# Comparators.net
KiCad netlist of a schematic drawn in Altium Designer
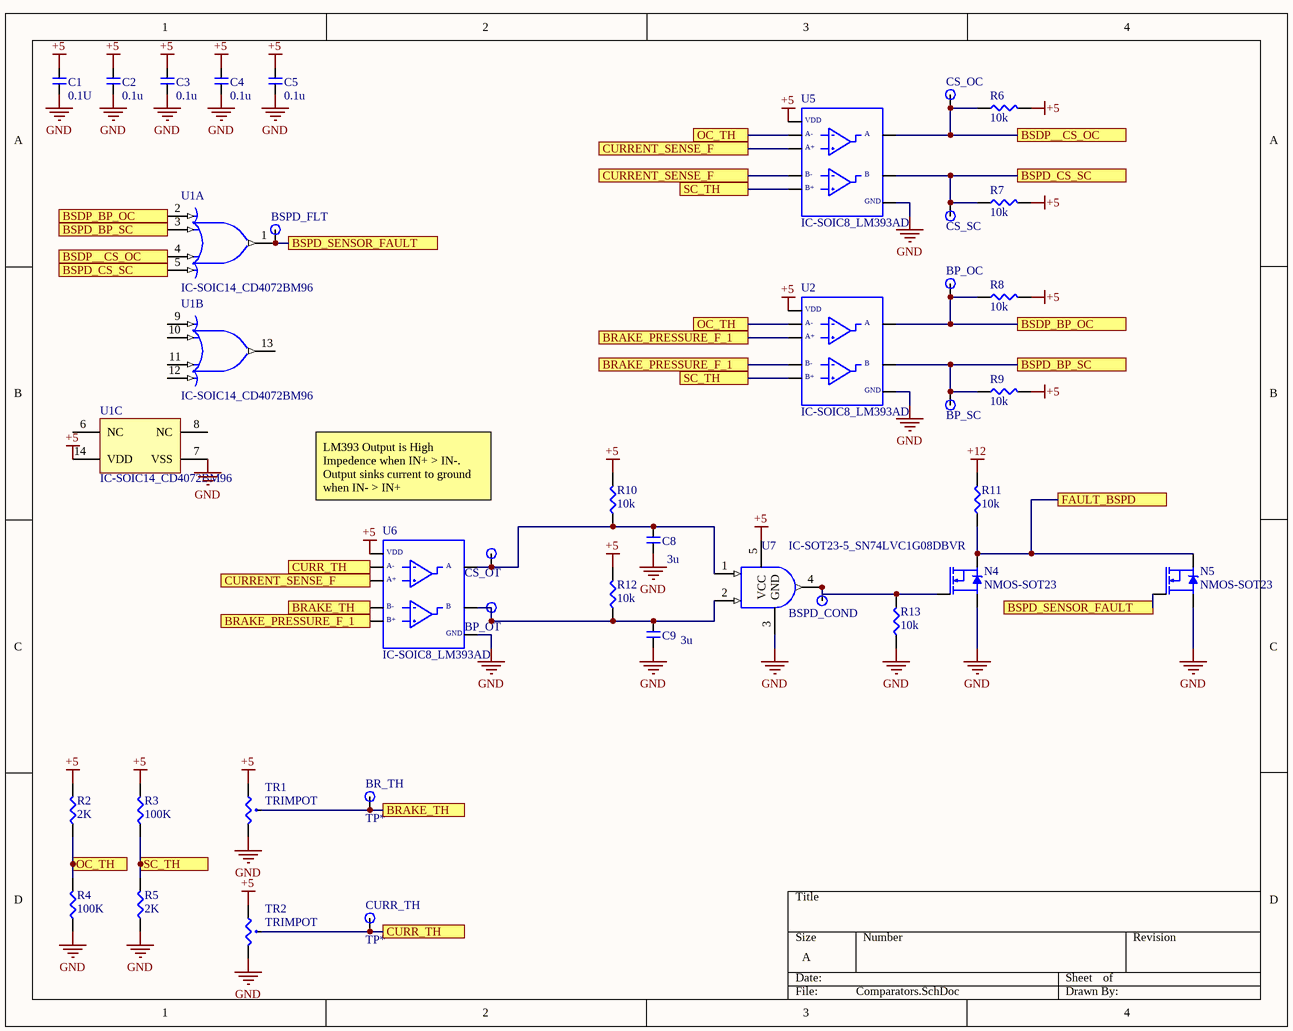
[diagram p0: Comparators.SchDoc]

(export (version "E")
  (design (tool "Eeschema 10.0.6"))
  (components
    (comp (ref "BP_OC")
      (value "~")
      (footprint "Testpoint")
      (libsource (lib "ife19_Elec_Library") (part "Testpoint"))
    )
    (comp (ref "BP_OT")
      (value "~")
      (footprint "Testpoint")
      (libsource (lib "ife19_Elec_Library") (part "Testpoint"))
    )
    (comp (ref "BP_SC")
      (value "~")
      (footprint "Testpoint")
      (libsource (lib "ife19_Elec_Library") (part "Testpoint"))
    )
    (comp (ref "BR_TH")
      (value "TP*")
      (footprint "Testpoint")
      (libsource (lib "ife19_Elec_Library") (part "Testpoint"))
    )
    (comp (ref "BSPD_COND")
      (value "~")
      (footprint "Testpoint")
      (libsource (lib "ife19_Elec_Library") (part "Testpoint"))
    )
    (comp (ref "BSPD_FLT")
      (value "~")
      (footprint "Testpoint")
      (libsource (lib "ife19_Elec_Library") (part "Testpoint"))
    )
    (comp (ref "C1")
      (value "0.1U")
      (footprint "ife19_Elec_Library:CAP-0603")
      (libsource (lib "ife19_Elec_Library") (part "CAP-0603"))
    )
    (comp (ref "C2")
      (value "0.1u")
      (footprint "CAP-0603")
      (libsource (lib "ife19_Elec_Library") (part "CAP-0603"))
    )
    (comp (ref "C3")
      (value "0.1u")
      (footprint "CAP-0603")
      (libsource (lib "ife19_Elec_Library") (part "CAP-0603"))
    )
    (comp (ref "C4")
      (value "0.1u")
      (footprint "CAP-0603")
      (libsource (lib "ife19_Elec_Library") (part "CAP-0603"))
    )
    (comp (ref "C5")
      (value "0.1u")
      (footprint "CAP-0603")
      (libsource (lib "ife19_Elec_Library") (part "CAP-0603"))
    )
    (comp (ref "C8")
      (value "3u")
      (footprint "CAP-0603")
      (libsource (lib "ife19_Elec_Library") (part "CAP-0603"))
    )
    (comp (ref "C9")
      (value "3u")
      (footprint "CAP-0603")
      (libsource (lib "ife19_Elec_Library") (part "CAP-0603"))
    )
    (comp (ref "CS_OC")
      (value "~")
      (footprint "Testpoint")
      (libsource (lib "ife19_Elec_Library") (part "Testpoint"))
    )
    (comp (ref "CS_OT")
      (value "~")
      (footprint "Testpoint")
      (libsource (lib "ife19_Elec_Library") (part "Testpoint"))
    )
    (comp (ref "CS_SC")
      (value "~")
      (footprint "Testpoint")
      (libsource (lib "ife19_Elec_Library") (part "Testpoint"))
    )
    (comp (ref "CURR_TH")
      (value "TP*")
      (footprint "Testpoint")
      (libsource (lib "ife19_Elec_Library") (part "Testpoint"))
    )
    (comp (ref "N4")
      (value "NMOS-SOT23")
      (footprint "SOT23")
      (libsource (lib "ife19_Elec_Library") (part "NMOS-SOT23"))
    )
    (comp (ref "N5")
      (value "NMOS-SOT23")
      (footprint "SOT23")
      (libsource (lib "ife19_Elec_Library") (part "NMOS-SOT23"))
    )
    (comp (ref "R2")
      (value "2K")
      (footprint "RES-0603")
      (libsource (lib "ife19_Elec_Library") (part "RES-0603"))
    )
    (comp (ref "R3")
      (value "100K")
      (footprint "RES-0603")
      (libsource (lib "ife19_Elec_Library") (part "RES-0603"))
    )
    (comp (ref "R4")
      (value "100K")
      (footprint "RES-0603")
      (libsource (lib "ife19_Elec_Library") (part "RES-0603"))
    )
    (comp (ref "R5")
      (value "2K")
      (footprint "RES-0603")
      (libsource (lib "ife19_Elec_Library") (part "RES-0603"))
    )
    (comp (ref "R6")
      (value "10k")
      (footprint "RES-0603")
      (libsource (lib "ife19_Elec_Library") (part "RES-0603"))
    )
    (comp (ref "R7")
      (value "10k")
      (footprint "RES-0603")
      (libsource (lib "ife19_Elec_Library") (part "RES-0603"))
    )
    (comp (ref "R8")
      (value "10k")
      (footprint "RES-0603")
      (libsource (lib "ife19_Elec_Library") (part "RES-0603"))
    )
    (comp (ref "R9")
      (value "10k")
      (footprint "RES-0603")
      (libsource (lib "ife19_Elec_Library") (part "RES-0603"))
    )
    (comp (ref "R10")
      (value "10k")
      (footprint "RES-0603")
      (libsource (lib "ife19_Elec_Library") (part "RES-0603"))
    )
    (comp (ref "R11")
      (value "10k")
      (footprint "RES-0603")
      (libsource (lib "ife19_Elec_Library") (part "RES-0603"))
    )
    (comp (ref "R12")
      (value "10k")
      (footprint "RES-0603")
      (libsource (lib "ife19_Elec_Library") (part "RES-0603"))
    )
    (comp (ref "R13")
      (value "10k")
      (footprint "RES-0603")
      (libsource (lib "ife19_Elec_Library") (part "RES-0603"))
    )
    (comp (ref "TR1")
      (value "TRIMPOT")
      (footprint "TRIMPOT_PV36W")
      (libsource (lib "ife19_Elec_Library") (part "TRIMPOT_PV36W"))
    )
    (comp (ref "TR2")
      (value "TRIMPOT")
      (footprint "TRIMPOT_PV36W")
      (libsource (lib "ife19_Elec_Library") (part "TRIMPOT_PV36W"))
    )
    (comp (ref "U1")
      (value "IC-SOIC14_CD4072BM96")
      (footprint "SOIC127P600X175-14N")
      (description "Logic Gates CMOS Dual 4-Input OR")
      (fields
        (field (name "MANUFACTURER PART NUMBER") "CD4072BM96")
        (field (name "MANUFACTURER") "Texas Instruments")
        (field (name "SOURCE") "ife19_Elec_Library.schlib")
      )
      (libsource (lib "Illini Formula Electric") (part "IC-SOIC14_CD4072BM96"))
    )
    (comp (ref "U2")
      (value "IC-SOIC8_LM393AD")
      (footprint "SOIC8")
      (libsource (lib "ife19_Elec_Library") (part "IC-SOIC8_LM393"))
    )
    (comp (ref "U5")
      (value "IC-SOIC8_LM393AD")
      (footprint "SOIC8")
      (libsource (lib "ife19_Elec_Library") (part "IC-SOIC8_LM393"))
    )
    (comp (ref "U6")
      (value "IC-SOIC8_LM393AD")
      (footprint "SOIC8")
      (libsource (lib "ife19_Elec_Library") (part "IC-SOIC8_LM393"))
    )
    (comp (ref "U7")
      (value "IC-SOT23-5_SN74LVC1G08DBVR")
      (footprint "SOT95P280X110-5N")
      (description "IC GATE AND 1CH 2-INP SOT23-5")
      (fields
        (field (name "MANUFACTURER") "Texas Instruments")
        (field (name "MANUFACTURER PART NUMBER") "SN74LVC1G08DBVR")
      )
      (libsource (lib "ife19_Elec_Library") (part "IC-SOT23-5_SN74LVC1G08DBVR"))
    )
  )
  (nets
    (net (code "1") (name "+5") (class "Default")
      (node (ref "C1") (pin "2") (pinfunction "2_2") (pintype "passive"))
      (node (ref "C2") (pin "2") (pinfunction "2_2") (pintype "passive"))
      (node (ref "C3") (pin "2") (pinfunction "2_2") (pintype "passive"))
      (node (ref "C4") (pin "2") (pinfunction "2_2") (pintype "passive"))
      (node (ref "C5") (pin "2") (pinfunction "2_2") (pintype "passive"))
      (node (ref "R10") (pin "2") (pinfunction "2_2") (pintype "passive"))
      (node (ref "R12") (pin "2") (pinfunction "2_2") (pintype "passive"))
      (node (ref "R2") (pin "2") (pinfunction "2_2") (pintype "passive"))
      (node (ref "R3") (pin "2") (pinfunction "2_2") (pintype "passive"))
      (node (ref "R6") (pin "2") (pinfunction "2_2") (pintype "passive"))
      (node (ref "R7") (pin "2") (pinfunction "2_2") (pintype "passive"))
      (node (ref "R8") (pin "2") (pinfunction "2_2") (pintype "passive"))
      (node (ref "R9") (pin "2") (pinfunction "2_2") (pintype "passive"))
      (node (ref "TR1") (pin "1") (pinfunction "1_1") (pintype "passive"))
      (node (ref "TR2") (pin "1") (pinfunction "1_1") (pintype "passive"))
      (node (ref "U1") (pin "14") (pinfunction "VDD_14") (pintype "power_in"))
      (node (ref "U2") (pin "8") (pinfunction "8_8") (pintype "passive"))
      (node (ref "U5") (pin "8") (pinfunction "8_8") (pintype "passive"))
      (node (ref "U6") (pin "8") (pinfunction "8_8") (pintype "passive"))
      (node (ref "U7") (pin "5") (pinfunction "VCC_5") (pintype "power_in"))
    )
    (net (code "2") (name "+12") (class "Default")
      (node (ref "R11") (pin "2") (pinfunction "2_2") (pintype "passive"))
    )
    (net (code "3") (name "/BRAKE_PRESSURE_F_1") (class "Default")
      (node (ref "U2") (pin "3") (pinfunction "3_3") (pintype "passive"))
      (node (ref "U2") (pin "6") (pinfunction "6_6") (pintype "passive"))
      (node (ref "U6") (pin "5") (pinfunction "5_5") (pintype "passive"))
    )
    (net (code "4") (name "/BRAKE_TH") (class "Default")
      (node (ref "BR_TH") (pin "1") (pinfunction "1_1") (pintype "passive"))
      (node (ref "TR1") (pin "2") (pinfunction "2_2") (pintype "passive"))
      (node (ref "U6") (pin "6") (pinfunction "6_6") (pintype "passive"))
    )
    (net (code "5") (name "/BSDP_BP_OC") (class "Default")
      (node (ref "BP_OC") (pin "1") (pinfunction "1_1") (pintype "passive"))
      (node (ref "R8") (pin "1") (pinfunction "1_1") (pintype "passive"))
      (node (ref "U1") (pin "2") (pinfunction "A_2") (pintype "input"))
      (node (ref "U2") (pin "1") (pinfunction "1_1") (pintype "passive"))
    )
    (net (code "6") (name "/BSDP__CS_OC") (class "Default")
      (node (ref "CS_OC") (pin "1") (pinfunction "1_1") (pintype "passive"))
      (node (ref "R6") (pin "1") (pinfunction "1_1") (pintype "passive"))
      (node (ref "U1") (pin "4") (pinfunction "C_4") (pintype "input"))
      (node (ref "U5") (pin "1") (pinfunction "1_1") (pintype "passive"))
    )
    (net (code "7") (name "/BSPD_BP_SC") (class "Default")
      (node (ref "BP_SC") (pin "1") (pinfunction "1_1") (pintype "passive"))
      (node (ref "R9") (pin "1") (pinfunction "1_1") (pintype "passive"))
      (node (ref "U1") (pin "3") (pinfunction "B_3") (pintype "input"))
      (node (ref "U2") (pin "7") (pinfunction "7_7") (pintype "passive"))
    )
    (net (code "8") (name "/BSPD_CS_SC") (class "Default")
      (node (ref "CS_SC") (pin "1") (pinfunction "1_1") (pintype "passive"))
      (node (ref "R7") (pin "1") (pinfunction "1_1") (pintype "passive"))
      (node (ref "U1") (pin "5") (pinfunction "D_5") (pintype "input"))
      (node (ref "U5") (pin "7") (pinfunction "7_7") (pintype "passive"))
    )
    (net (code "9") (name "/BSPD_SENSOR_FAULT") (class "Default")
      (node (ref "BSPD_FLT") (pin "1") (pinfunction "1_1") (pintype "passive"))
      (node (ref "N5") (pin "1") (pinfunction "G_1") (pintype "passive"))
      (node (ref "U1") (pin "1") (pinfunction "J_1") (pintype "output"))
    )
    (net (code "10") (name "/CURRENT_SENSE_F") (class "Default")
      (node (ref "U5") (pin "3") (pinfunction "3_3") (pintype "passive"))
      (node (ref "U5") (pin "6") (pinfunction "6_6") (pintype "passive"))
      (node (ref "U6") (pin "3") (pinfunction "3_3") (pintype "passive"))
    )
    (net (code "11") (name "/CURR_TH") (class "Default")
      (node (ref "CURR_TH") (pin "1") (pinfunction "1_1") (pintype "passive"))
      (node (ref "TR2") (pin "2") (pinfunction "2_2") (pintype "passive"))
      (node (ref "U6") (pin "2") (pinfunction "2_2") (pintype "passive"))
    )
    (net (code "12") (name "/FAULT_BSPD") (class "Default")
      (node (ref "N4") (pin "3") (pinfunction "D_3") (pintype "passive"))
      (node (ref "N5") (pin "3") (pinfunction "D_3") (pintype "passive"))
      (node (ref "R11") (pin "1") (pinfunction "1_1") (pintype "passive"))
    )
    (net (code "13") (name "/OC_TH") (class "Default")
      (node (ref "R2") (pin "1") (pinfunction "1_1") (pintype "passive"))
      (node (ref "R4") (pin "2") (pinfunction "2_2") (pintype "passive"))
      (node (ref "U2") (pin "2") (pinfunction "2_2") (pintype "passive"))
      (node (ref "U5") (pin "2") (pinfunction "2_2") (pintype "passive"))
    )
    (net (code "14") (name "/SC_TH") (class "Default")
      (node (ref "R3") (pin "1") (pinfunction "1_1") (pintype "passive"))
      (node (ref "R5") (pin "2") (pinfunction "2_2") (pintype "passive"))
      (node (ref "U2") (pin "5") (pinfunction "5_5") (pintype "passive"))
      (node (ref "U5") (pin "5") (pinfunction "5_5") (pintype "passive"))
    )
    (net (code "15") (name "GND") (class "Default")
      (node (ref "C1") (pin "1") (pinfunction "1_1") (pintype "passive"))
      (node (ref "C2") (pin "1") (pinfunction "1_1") (pintype "passive"))
      (node (ref "C3") (pin "1") (pinfunction "1_1") (pintype "passive"))
      (node (ref "C4") (pin "1") (pinfunction "1_1") (pintype "passive"))
      (node (ref "C5") (pin "1") (pinfunction "1_1") (pintype "passive"))
      (node (ref "C8") (pin "1") (pinfunction "1_1") (pintype "passive"))
      (node (ref "C9") (pin "1") (pinfunction "1_1") (pintype "passive"))
      (node (ref "N4") (pin "2") (pinfunction "S_2") (pintype "passive"))
      (node (ref "N5") (pin "2") (pinfunction "S_2") (pintype "passive"))
      (node (ref "R13") (pin "1") (pinfunction "1_1") (pintype "passive"))
      (node (ref "R4") (pin "1") (pinfunction "1_1") (pintype "passive"))
      (node (ref "R5") (pin "1") (pinfunction "1_1") (pintype "passive"))
      (node (ref "TR1") (pin "3") (pinfunction "3_3") (pintype "passive"))
      (node (ref "TR2") (pin "3") (pinfunction "3_3") (pintype "passive"))
      (node (ref "U1") (pin "7") (pinfunction "VSS_7") (pintype "power_in"))
      (node (ref "U2") (pin "4") (pinfunction "4_4") (pintype "passive"))
      (node (ref "U5") (pin "4") (pinfunction "4_4") (pintype "passive"))
      (node (ref "U6") (pin "4") (pinfunction "4_4") (pintype "passive"))
      (node (ref "U7") (pin "3") (pinfunction "GND_3") (pintype "power_in"))
    )
    (net (code "16") (name "Net-(N4-G)") (class "Default")
      (node (ref "BSPD_COND") (pin "1") (pinfunction "1_1") (pintype "passive"))
      (node (ref "N4") (pin "1") (pinfunction "G_1") (pintype "passive"))
      (node (ref "R13") (pin "2") (pinfunction "2_2") (pintype "passive"))
      (node (ref "U7") (pin "4") (pinfunction "Y_4") (pintype "output"))
    )
    (net (code "17") (name "Net-(U7-A)") (class "Default")
      (node (ref "C8") (pin "2") (pinfunction "2_2") (pintype "passive"))
      (node (ref "CS_OT") (pin "1") (pinfunction "1_1") (pintype "passive"))
      (node (ref "R10") (pin "1") (pinfunction "1_1") (pintype "passive"))
      (node (ref "U6") (pin "1") (pinfunction "1_1") (pintype "passive"))
      (node (ref "U7") (pin "1") (pinfunction "A_1") (pintype "input"))
    )
    (net (code "18") (name "Net-(U7-B)") (class "Default")
      (node (ref "BP_OT") (pin "1") (pinfunction "1_1") (pintype "passive"))
      (node (ref "C9") (pin "2") (pinfunction "2_2") (pintype "passive"))
      (node (ref "R12") (pin "1") (pinfunction "1_1") (pintype "passive"))
      (node (ref "U6") (pin "7") (pinfunction "7_7") (pintype "passive"))
      (node (ref "U7") (pin "2") (pinfunction "B_2") (pintype "input"))
    )
    (net (code "19") (name "unconnected-(U1B-E-Pad9)") (class "Default")
      (node (ref "U1") (pin "9") (pinfunction "E_9") (pintype "input"))
    )
    (net (code "20") (name "unconnected-(U1B-F-Pad10)") (class "Default")
      (node (ref "U1") (pin "10") (pinfunction "F_10") (pintype "input"))
    )
    (net (code "21") (name "unconnected-(U1B-G-Pad11)") (class "Default")
      (node (ref "U1") (pin "11") (pinfunction "G_11") (pintype "input"))
    )
    (net (code "22") (name "unconnected-(U1B-H-Pad12)") (class "Default")
      (node (ref "U1") (pin "12") (pinfunction "H_12") (pintype "input"))
    )
    (net (code "23") (name "unconnected-(U1B-K-Pad13)") (class "Default")
      (node (ref "U1") (pin "13") (pinfunction "K_13") (pintype "output"))
    )
    (net (code "24") (name "unconnected-(U1C-NC-Pad6)") (class "Default")
      (node (ref "U1") (pin "6") (pinfunction "NC_6") (pintype "passive"))
    )
    (net (code "25") (name "unconnected-(U1C-NC-Pad8)") (class "Default")
      (node (ref "U1") (pin "8") (pinfunction "NC_8") (pintype "passive"))
    )
  )
)
